# DigitalClockSegmentDisplay_Separator.net
KiCad netlist of a schematic drawn in EAGLE
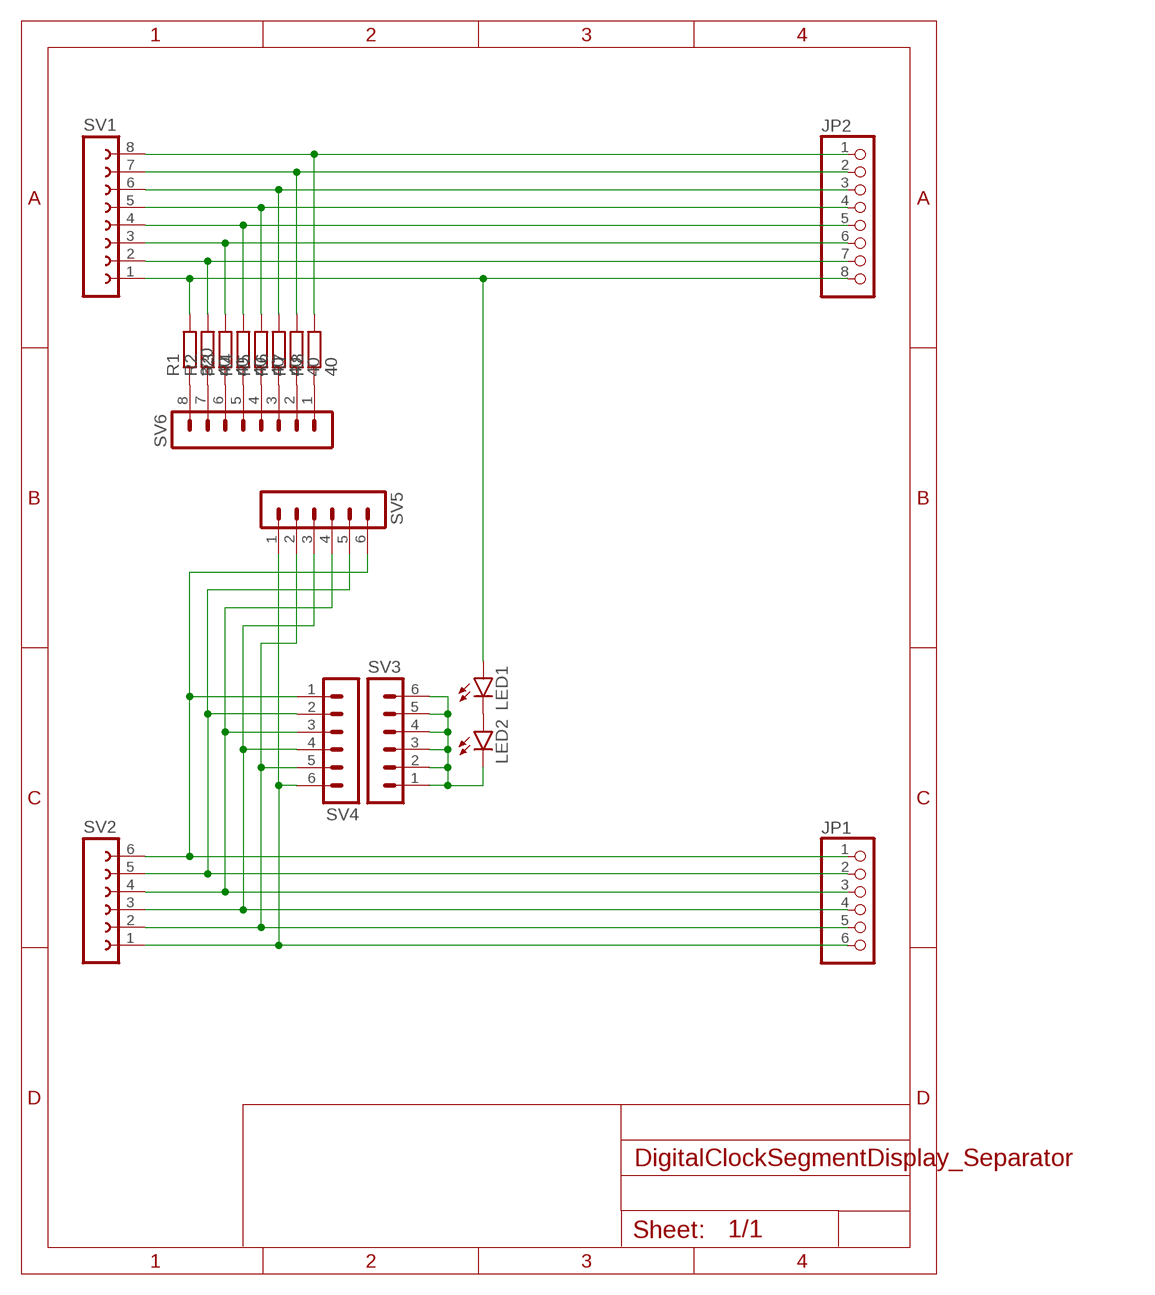
[diagram p0: schematic, sheet 1]

(export (version "E")
  (design (tool "Eeschema 10.0.6"))
  (components
    (comp (ref "JP1")
      (value "PINHD-1X6/90")
      (footprint "eagle-import:1X06_90")
      (libsource (lib "eagle-import") (part "PINHD-1X6/90"))
    )
    (comp (ref "JP2")
      (value "PINHD-1X8/90")
      (footprint "eagle-import:1X08_90")
      (libsource (lib "eagle-import") (part "PINHD-1X8/90"))
    )
    (comp (ref "LED1")
      (value "LED5MM")
      (footprint "eagle-import:LED5MM")
      (libsource (lib "eagle-import") (part "LED5MM"))
    )
    (comp (ref "LED2")
      (value "LED5MM")
      (footprint "eagle-import:LED5MM")
      (libsource (lib "eagle-import") (part "LED5MM"))
    )
    (comp (ref "R1")
      (value "320")
      (footprint "eagle-import:0207_10")
      (libsource (lib "eagle-import") (part "R-EU_0207/10"))
    )
    (comp (ref "R2")
      (value "40")
      (footprint "eagle-import:0207_10")
      (libsource (lib "eagle-import") (part "R-EU_0207/10"))
    )
    (comp (ref "R3")
      (value "40")
      (footprint "eagle-import:0207_10")
      (libsource (lib "eagle-import") (part "R-EU_0207/10"))
    )
    (comp (ref "R4")
      (value "40")
      (footprint "eagle-import:0207_10")
      (libsource (lib "eagle-import") (part "R-EU_0207/10"))
    )
    (comp (ref "R5")
      (value "40")
      (footprint "eagle-import:0207_10")
      (libsource (lib "eagle-import") (part "R-EU_0207/10"))
    )
    (comp (ref "R6")
      (value "40")
      (footprint "eagle-import:0207_10")
      (libsource (lib "eagle-import") (part "R-EU_0207/10"))
    )
    (comp (ref "R7")
      (value "40")
      (footprint "eagle-import:0207_10")
      (libsource (lib "eagle-import") (part "R-EU_0207/10"))
    )
    (comp (ref "R8")
      (value "40")
      (footprint "eagle-import:0207_10")
      (libsource (lib "eagle-import") (part "R-EU_0207/10"))
    )
    (comp (ref "SV1")
      (value "FE08W")
      (footprint "eagle-import:FE08W")
      (libsource (lib "eagle-import") (part "FE08W"))
    )
    (comp (ref "SV2")
      (value "FE06W")
      (footprint "eagle-import:FE06W")
      (libsource (lib "eagle-import") (part "FE06W"))
    )
    (comp (ref "SV3")
      (value "MA06-1")
      (footprint "eagle-import:MA06-1")
      (libsource (lib "eagle-import") (part "MA06-1"))
    )
    (comp (ref "SV4")
      (value "MA06-1")
      (footprint "eagle-import:MA06-1")
      (libsource (lib "eagle-import") (part "MA06-1"))
    )
    (comp (ref "SV5")
      (value "MA06-1")
      (footprint "eagle-import:MA06-1")
      (libsource (lib "eagle-import") (part "MA06-1"))
    )
    (comp (ref "SV6")
      (value "MA08-1")
      (footprint "eagle-import:MA08-1")
      (libsource (lib "eagle-import") (part "MA08-1"))
    )
  )
  (nets
    (net (code "1") (name "Net-(JP1-Pad1)") (class "Default")
      (node (ref "JP1") (pin "1") (pinfunction "1_1") (pintype "passive"))
      (node (ref "SV2") (pin "6") (pinfunction "6_6") (pintype "passive"))
      (node (ref "SV4") (pin "1") (pinfunction "1_1") (pintype "passive"))
      (node (ref "SV5") (pin "6") (pinfunction "6_6") (pintype "passive"))
    )
    (net (code "2") (name "Net-(JP1-Pad2)") (class "Default")
      (node (ref "JP1") (pin "2") (pinfunction "2_2") (pintype "passive"))
      (node (ref "SV2") (pin "5") (pinfunction "5_5") (pintype "passive"))
      (node (ref "SV4") (pin "2") (pinfunction "2_2") (pintype "passive"))
      (node (ref "SV5") (pin "5") (pinfunction "5_5") (pintype "passive"))
    )
    (net (code "3") (name "Net-(JP1-Pad3)") (class "Default")
      (node (ref "JP1") (pin "3") (pinfunction "3_3") (pintype "passive"))
      (node (ref "SV2") (pin "4") (pinfunction "4_4") (pintype "passive"))
      (node (ref "SV4") (pin "3") (pinfunction "3_3") (pintype "passive"))
      (node (ref "SV5") (pin "4") (pinfunction "4_4") (pintype "passive"))
    )
    (net (code "4") (name "Net-(JP1-Pad4)") (class "Default")
      (node (ref "JP1") (pin "4") (pinfunction "4_4") (pintype "passive"))
      (node (ref "SV2") (pin "3") (pinfunction "3_3") (pintype "passive"))
      (node (ref "SV4") (pin "4") (pinfunction "4_4") (pintype "passive"))
      (node (ref "SV5") (pin "3") (pinfunction "3_3") (pintype "passive"))
    )
    (net (code "5") (name "Net-(JP1-Pad5)") (class "Default")
      (node (ref "JP1") (pin "5") (pinfunction "5_5") (pintype "passive"))
      (node (ref "SV2") (pin "2") (pinfunction "2_2") (pintype "passive"))
      (node (ref "SV4") (pin "5") (pinfunction "5_5") (pintype "passive"))
      (node (ref "SV5") (pin "2") (pinfunction "2_2") (pintype "passive"))
    )
    (net (code "6") (name "Net-(JP1-Pad6)") (class "Default")
      (node (ref "JP1") (pin "6") (pinfunction "6_6") (pintype "passive"))
      (node (ref "SV2") (pin "1") (pinfunction "1_1") (pintype "passive"))
      (node (ref "SV4") (pin "6") (pinfunction "6_6") (pintype "passive"))
      (node (ref "SV5") (pin "1") (pinfunction "1_1") (pintype "passive"))
    )
    (net (code "7") (name "Net-(JP2-Pad1)") (class "Default")
      (node (ref "JP2") (pin "1") (pinfunction "1_1") (pintype "passive"))
      (node (ref "R8") (pin "2") (pinfunction "2_2") (pintype "passive"))
      (node (ref "SV1") (pin "8") (pinfunction "8_8") (pintype "passive"))
    )
    (net (code "8") (name "Net-(JP2-Pad2)") (class "Default")
      (node (ref "JP2") (pin "2") (pinfunction "2_2") (pintype "passive"))
      (node (ref "R7") (pin "2") (pinfunction "2_2") (pintype "passive"))
      (node (ref "SV1") (pin "7") (pinfunction "7_7") (pintype "passive"))
    )
    (net (code "9") (name "Net-(JP2-Pad3)") (class "Default")
      (node (ref "JP2") (pin "3") (pinfunction "3_3") (pintype "passive"))
      (node (ref "R6") (pin "2") (pinfunction "2_2") (pintype "passive"))
      (node (ref "SV1") (pin "6") (pinfunction "6_6") (pintype "passive"))
    )
    (net (code "10") (name "Net-(JP2-Pad4)") (class "Default")
      (node (ref "JP2") (pin "4") (pinfunction "4_4") (pintype "passive"))
      (node (ref "R5") (pin "2") (pinfunction "2_2") (pintype "passive"))
      (node (ref "SV1") (pin "5") (pinfunction "5_5") (pintype "passive"))
    )
    (net (code "11") (name "Net-(JP2-Pad5)") (class "Default")
      (node (ref "JP2") (pin "5") (pinfunction "5_5") (pintype "passive"))
      (node (ref "R4") (pin "2") (pinfunction "2_2") (pintype "passive"))
      (node (ref "SV1") (pin "4") (pinfunction "4_4") (pintype "passive"))
    )
    (net (code "12") (name "Net-(JP2-Pad6)") (class "Default")
      (node (ref "JP2") (pin "6") (pinfunction "6_6") (pintype "passive"))
      (node (ref "R3") (pin "2") (pinfunction "2_2") (pintype "passive"))
      (node (ref "SV1") (pin "3") (pinfunction "3_3") (pintype "passive"))
    )
    (net (code "13") (name "Net-(JP2-Pad7)") (class "Default")
      (node (ref "JP2") (pin "7") (pinfunction "7_7") (pintype "passive"))
      (node (ref "R2") (pin "2") (pinfunction "2_2") (pintype "passive"))
      (node (ref "SV1") (pin "2") (pinfunction "2_2") (pintype "passive"))
    )
    (net (code "14") (name "Net-(JP2-Pad8)") (class "Default")
      (node (ref "JP2") (pin "8") (pinfunction "8_8") (pintype "passive"))
      (node (ref "LED1") (pin "A") (pinfunction "A_A") (pintype "passive"))
      (node (ref "R1") (pin "2") (pinfunction "2_2") (pintype "passive"))
      (node (ref "SV1") (pin "1") (pinfunction "1_1") (pintype "passive"))
    )
    (net (code "15") (name "Net-(LED1-C)") (class "Default")
      (node (ref "LED1") (pin "K") (pinfunction "C_K") (pintype "passive"))
      (node (ref "LED2") (pin "A") (pinfunction "A_A") (pintype "passive"))
    )
    (net (code "16") (name "Net-(LED2-C)") (class "Default")
      (node (ref "LED2") (pin "K") (pinfunction "C_K") (pintype "passive"))
      (node (ref "SV3") (pin "1") (pinfunction "1_1") (pintype "passive"))
      (node (ref "SV3") (pin "2") (pinfunction "2_2") (pintype "passive"))
      (node (ref "SV3") (pin "3") (pinfunction "3_3") (pintype "passive"))
      (node (ref "SV3") (pin "4") (pinfunction "4_4") (pintype "passive"))
      (node (ref "SV3") (pin "5") (pinfunction "5_5") (pintype "passive"))
      (node (ref "SV3") (pin "6") (pinfunction "6_6") (pintype "passive"))
    )
    (net (code "17") (name "Net-(R1-Pad1)") (class "Default")
      (node (ref "R1") (pin "1") (pinfunction "1_1") (pintype "passive"))
      (node (ref "SV6") (pin "8") (pinfunction "8_8") (pintype "passive"))
    )
    (net (code "18") (name "Net-(R2-Pad1)") (class "Default")
      (node (ref "R2") (pin "1") (pinfunction "1_1") (pintype "passive"))
      (node (ref "SV6") (pin "7") (pinfunction "7_7") (pintype "passive"))
    )
    (net (code "19") (name "Net-(R3-Pad1)") (class "Default")
      (node (ref "R3") (pin "1") (pinfunction "1_1") (pintype "passive"))
      (node (ref "SV6") (pin "6") (pinfunction "6_6") (pintype "passive"))
    )
    (net (code "20") (name "Net-(R4-Pad1)") (class "Default")
      (node (ref "R4") (pin "1") (pinfunction "1_1") (pintype "passive"))
      (node (ref "SV6") (pin "5") (pinfunction "5_5") (pintype "passive"))
    )
    (net (code "21") (name "Net-(R5-Pad1)") (class "Default")
      (node (ref "R5") (pin "1") (pinfunction "1_1") (pintype "passive"))
      (node (ref "SV6") (pin "4") (pinfunction "4_4") (pintype "passive"))
    )
    (net (code "22") (name "Net-(R6-Pad1)") (class "Default")
      (node (ref "R6") (pin "1") (pinfunction "1_1") (pintype "passive"))
      (node (ref "SV6") (pin "3") (pinfunction "3_3") (pintype "passive"))
    )
    (net (code "23") (name "Net-(R7-Pad1)") (class "Default")
      (node (ref "R7") (pin "1") (pinfunction "1_1") (pintype "passive"))
      (node (ref "SV6") (pin "2") (pinfunction "2_2") (pintype "passive"))
    )
    (net (code "24") (name "Net-(R8-Pad1)") (class "Default")
      (node (ref "R8") (pin "1") (pinfunction "1_1") (pintype "passive"))
      (node (ref "SV6") (pin "1") (pinfunction "1_1") (pintype "passive"))
    )
  )
)
